# Controller.net
KiCad netlist of a schematic drawn in Altium Designer
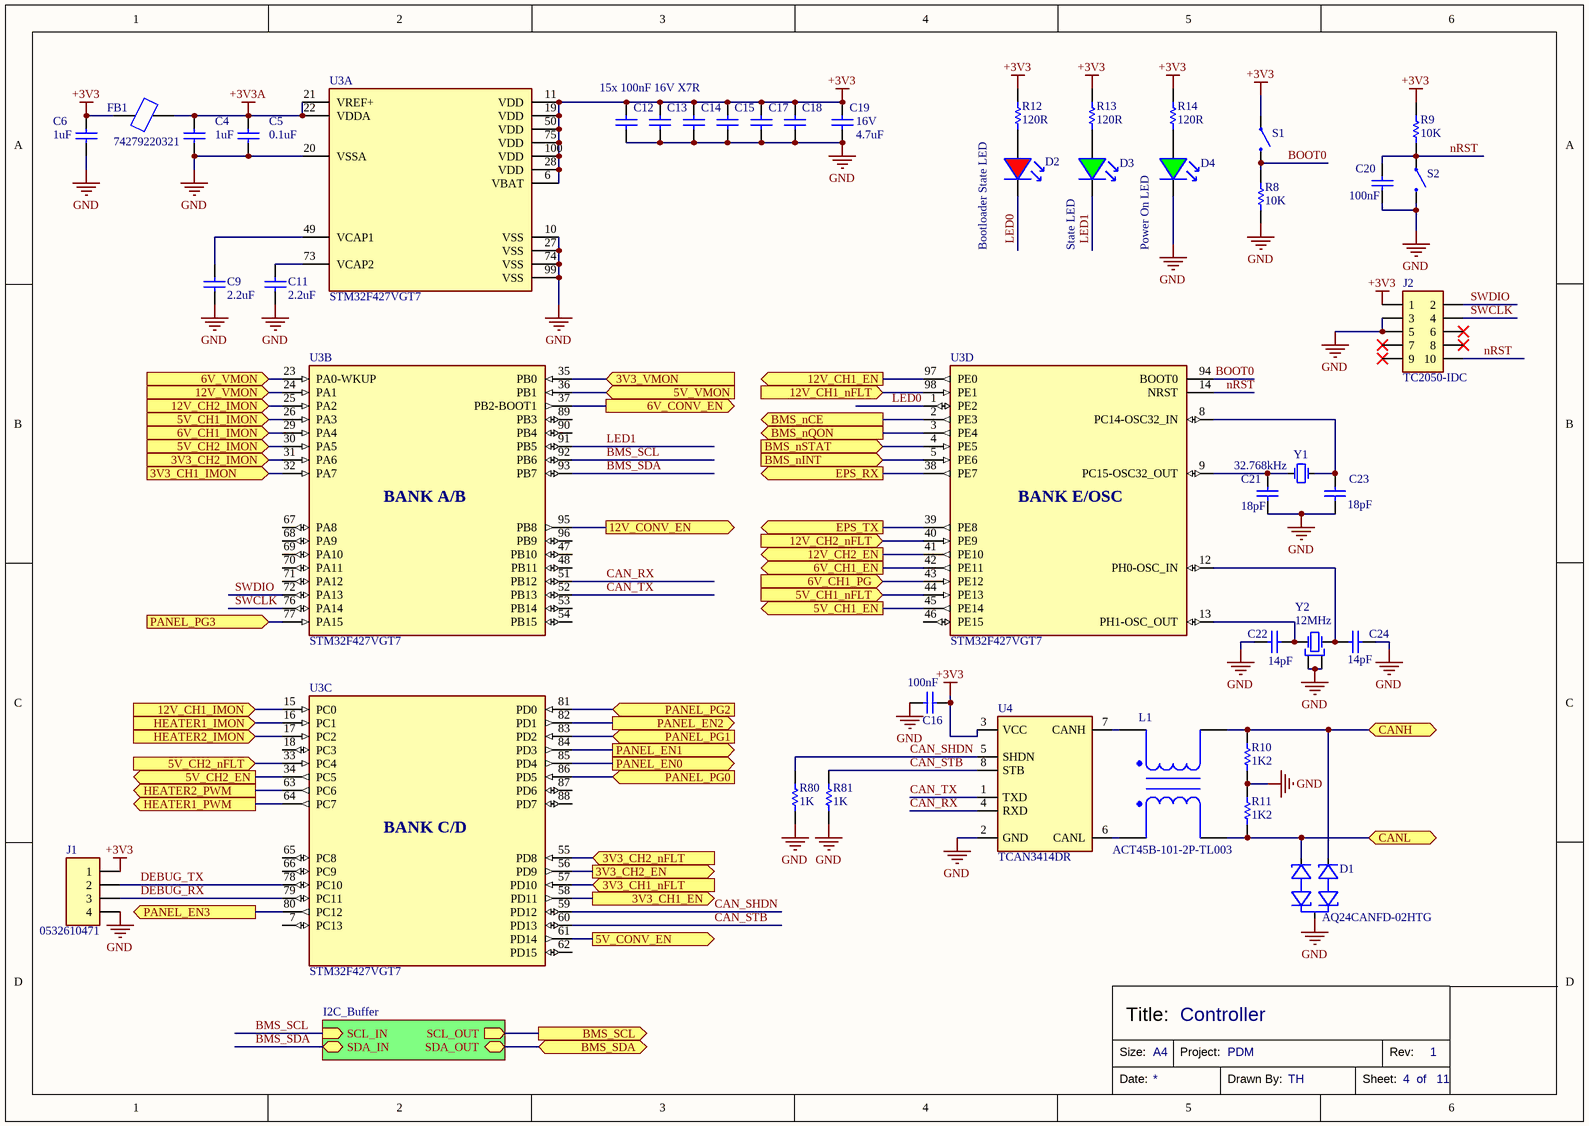
[diagram p0: Controller.SchDoc]

(export (version "E")
  (design (tool "Eeschema 10.0.6"))
  (components
    (comp (ref "C4")
      (value "CL10B105KO8NNNC")
      (footprint "CAPC0603X040")
      (description "1 µF ±10% 16V Ceramic Capacitor X7R 0603 (1608 Metric)")
      (fields
        (field (name "TOLERANCE") "10%")
        (field (name "DISTRIBUTOR PART NUMBER") "1276-1019-1-ND")
        (field (name "CAPACITANCE") "1uF")
      )
      (libsource (lib "Ahristi_Library") (part "CAPC0603"))
    )
    (comp (ref "C5")
      (value "CL05B104KB5NNNC")
      (footprint "CAPC0402X020")
      (description "0.1 µF ±10% 50V Ceramic Capacitor X7R 0402 (1005 Metric)")
      (fields
        (field (name "TOLERANCE") "10%")
        (field (name "DISTRIBUTOR PART NUMBER") "1276-CL05B104KB5NNNCCT-ND")
        (field (name "CAPACITANCE") "0.1uF")
      )
      (libsource (lib "Ahristi_Library") (part "CL05B104KB5NNNC"))
    )
    (comp (ref "C6")
      (value "CL10B105KO8NNNC")
      (footprint "CAPC0603X040")
      (description "1 µF ±10% 16V Ceramic Capacitor X7R 0603 (1608 Metric)")
      (fields
        (field (name "TOLERANCE") "10%")
        (field (name "DISTRIBUTOR PART NUMBER") "1276-1019-1-ND")
        (field (name "CAPACITANCE") "1uF")
      )
      (libsource (lib "Ahristi_Library") (part "CAPC0603"))
    )
    (comp (ref "C9")
      (value "CL21A225KBFNNNE")
      (footprint "CAPC0805X060")
      (description "2.2uF ±10% 25V Ceramic Capacitor X7R 0805 (2012 Metric)")
      (fields
        (field (name "DISTRIBUTOR PART NUMBER") "1276-6702-1-ND")
        (field (name "TOLERANCE") "10%")
        (field (name "CAPACITANCE") "2.2uF")
      )
      (libsource (lib "Ahristi_Library") (part "CL21A225KBFNNNE"))
    )
    (comp (ref "C11")
      (value "CL21A225KBFNNNE")
      (footprint "CAPC0805X060")
      (description "2.2uF ±10% 25V Ceramic Capacitor X7R 0805 (2012 Metric)")
      (fields
        (field (name "DISTRIBUTOR PART NUMBER") "1276-6702-1-ND")
        (field (name "TOLERANCE") "10%")
        (field (name "CAPACITANCE") "2.2uF")
      )
      (libsource (lib "Ahristi_Library") (part "CL21A225KBFNNNE"))
    )
    (comp (ref "C12")
      (value "CL05B104KB5NNNC")
      (footprint "CAPC0402X020")
      (description "0.1 µF ±10% 50V Ceramic Capacitor X7R 0402 (1005 Metric)")
      (fields
        (field (name "TOLERANCE") "10%")
        (field (name "DISTRIBUTOR PART NUMBER") "1276-CL05B104KB5NNNCCT-ND")
      )
      (libsource (lib "Ahristi_Library") (part "CL05B104KB5NNNC"))
    )
    (comp (ref "C13")
      (value "CL05B104KB5NNNC")
      (footprint "CAPC0402X020")
      (description "0.1 µF ±10% 50V Ceramic Capacitor X7R 0402 (1005 Metric)")
      (fields
        (field (name "TOLERANCE") "10%")
        (field (name "DISTRIBUTOR PART NUMBER") "1276-CL05B104KB5NNNCCT-ND")
      )
      (libsource (lib "Ahristi_Library") (part "CL05B104KB5NNNC"))
    )
    (comp (ref "C14")
      (value "CL05B104KB5NNNC")
      (footprint "CAPC0402X020")
      (description "0.1 µF ±10% 50V Ceramic Capacitor X7R 0402 (1005 Metric)")
      (fields
        (field (name "TOLERANCE") "10%")
        (field (name "DISTRIBUTOR PART NUMBER") "1276-CL05B104KB5NNNCCT-ND")
      )
      (libsource (lib "Ahristi_Library") (part "CL05B104KB5NNNC"))
    )
    (comp (ref "C15")
      (value "CL05B104KB5NNNC")
      (footprint "CAPC0402X020")
      (description "0.1 µF ±10% 50V Ceramic Capacitor X7R 0402 (1005 Metric)")
      (fields
        (field (name "TOLERANCE") "10%")
        (field (name "DISTRIBUTOR PART NUMBER") "1276-CL05B104KB5NNNCCT-ND")
      )
      (libsource (lib "Ahristi_Library") (part "CL05B104KB5NNNC"))
    )
    (comp (ref "C16")
      (value "C0603C104K5RACTU")
      (footprint "CAPC0603X040")
      (description "0.1 µF ±10% 50V Ceramic Capacitor X7R 0603 (1608 Metric)")
      (fields
        (field (name "TOLERANCE") "10%")
        (field (name "DISTRIBUTOR PART NUMBER") "399-C0603C104K5RACTUCT-ND")
        (field (name "CAPACITANCE") "100nF")
      )
      (libsource (lib "Ahristi_Library") (part "C0603C104K5RACTU"))
    )
    (comp (ref "C17")
      (value "CL05B104KB5NNNC")
      (footprint "CAPC0402X020")
      (description "0.1 µF ±10% 50V Ceramic Capacitor X7R 0402 (1005 Metric)")
      (fields
        (field (name "TOLERANCE") "10%")
        (field (name "DISTRIBUTOR PART NUMBER") "1276-CL05B104KB5NNNCCT-ND")
      )
      (libsource (lib "Ahristi_Library") (part "CL05B104KB5NNNC"))
    )
    (comp (ref "C18")
      (value "CL05B104KB5NNNC")
      (footprint "CAPC0402X020")
      (description "0.1 µF ±10% 50V Ceramic Capacitor X7R 0402 (1005 Metric)")
      (fields
        (field (name "TOLERANCE") "10%")
        (field (name "DISTRIBUTOR PART NUMBER") "1276-CL05B104KB5NNNCCT-ND")
      )
      (libsource (lib "Ahristi_Library") (part "CL05B104KB5NNNC"))
    )
    (comp (ref "C19")
      (value "CL21B475KOFNFNE")
      (footprint "CAPC0805X060")
      (description "4.7 µF ±10% 16V Ceramic Capacitor X7R 0805 (2012 Metric)")
      (fields
        (field (name "DISTRIBUTOR PART NUMBER") "1276-2970-1-ND")
        (field (name "TOLERANCE") "10%")
        (field (name "VOLTAGE RATING") "16V")
        (field (name "CAPACITANCE") "4.7uF")
      )
      (libsource (lib "Ahristi_Library") (part "CL21B475KOFNFNE"))
    )
    (comp (ref "C20")
      (value "C0603C104K5RACTU")
      (footprint "CAPC0603X040")
      (description "0.1 µF ±10% 50V Ceramic Capacitor X7R 0603 (1608 Metric)")
      (fields
        (field (name "TOLERANCE") "10%")
        (field (name "DISTRIBUTOR PART NUMBER") "399-C0603C104K5RACTUCT-ND")
        (field (name "CAPACITANCE") "100nF")
      )
      (libsource (lib "Ahristi_Library") (part "C0603C104K5RACTU"))
    )
    (comp (ref "C21")
      (value "KGM05ACG1H180FH")
      (footprint "CAPC0402X020")
      (description "18 pF ±1% 50V Ceramic Capacitor C0G, NP0 0402 (1005 Metric)")
      (fields
        (field (name "TOLERANCE") "1%")
        (field (name "DISTRIBUTOR PART NUMBER") "478-KGM05ACG1H180FHCT-ND")
        (field (name "CAPACITANCE") "18pF")
      )
      (libsource (lib "Ahristi_Library") (part "CAPC0402"))
    )
    (comp (ref "C22")
      (value "GJM1555C1H140FB01D")
      (footprint "CAPC0402X020")
      (description "14 pF ±1% 50V Ceramic Capacitor C0G, NP0 0402 (1005 Metric)")
      (fields
        (field (name "TOLERANCE") "1%")
        (field (name "DISTRIBUTOR PART NUMBER") "2266-GJM1555C1H140FB01DTR-ND")
        (field (name "CAPACITANCE") "14pF")
      )
      (libsource (lib "Ahristi_Library") (part "CAPC0402"))
    )
    (comp (ref "C23")
      (value "KGM05ACG1H180FH")
      (footprint "CAPC0402X020")
      (description "18 pF ±1% 50V Ceramic Capacitor C0G, NP0 0402 (1005 Metric)")
      (fields
        (field (name "TOLERANCE") "1%")
        (field (name "DISTRIBUTOR PART NUMBER") "478-KGM05ACG1H180FHCT-ND")
        (field (name "CAPACITANCE") "18pF")
      )
      (libsource (lib "Ahristi_Library") (part "CAPC0402"))
    )
    (comp (ref "C24")
      (value "GJM1555C1H140FB01D")
      (footprint "CAPC0402X020")
      (description "14 pF ±1% 50V Ceramic Capacitor C0G, NP0 0402 (1005 Metric)")
      (fields
        (field (name "TOLERANCE") "1%")
        (field (name "DISTRIBUTOR PART NUMBER") "2266-GJM1555C1H140FB01DTR-ND")
        (field (name "CAPACITANCE") "14pF")
      )
      (libsource (lib "Ahristi_Library") (part "CAPC0402"))
    )
    (comp (ref "D1")
      (value "AQ24CANFD-02HTG")
      (footprint "SOT23-3 IC")
      (description "50V Clamp 3A (8/20µs) Ipp Tvs Diode Surface Mount SOT-23-3")
      (fields (field (name "DISTRIBUTOR PART NUMBER") "F10993CT-ND"))
      (libsource (lib "Ahristi_Library") (part "AQ24CANFD-02HTG"))
    )
    (comp (ref "D2")
      (value "LTST-C170EKT")
      (footprint "LEDR_0805")
      (description "Red 621nm LED Indication - Discrete 2V 0805 (2012 Metric)")
      (fields (field (name "DISTRIBUTOR PART NUMBER") "160-1178-1-ND"))
      (libsource (lib "Ahristi_Library") (part "LEDR0805"))
    )
    (comp (ref "D3")
      (value "LTST-C170GKT")
      (footprint "LEDG_0805")
      (description "Green 569nm LED Indication - Discrete 2.1V 0805 (2012 Metric)")
      (fields (field (name "DISTRIBUTOR PART NUMBER") "160-1179-1-ND"))
      (libsource (lib "Ahristi_Library") (part "LEDG0805"))
    )
    (comp (ref "D4")
      (value "LTST-C170GKT")
      (footprint "LEDG_0805")
      (description "Green 569nm LED Indication - Discrete 2.1V 0805 (2012 Metric)")
      (fields (field (name "DISTRIBUTOR PART NUMBER") "160-1179-1-ND"))
      (libsource (lib "Ahristi_Library") (part "LEDG0805"))
    )
    (comp (ref "FB1")
      (value "74279220321")
      (footprint "74279220321")
      (description "Ferrite Bead 320 Ohms @ 100 MHz 1 Ferrite Bead 0805 (2012 Metric) 2.5A 50mOhm")
      (fields (field (name "DISTRIBUTOR PART NUMBER") "732-6125-1-ND"))
      (libsource (lib "Ahristi_Library") (part "74279220321"))
    )
    (comp (ref "J1")
      (value "0532610471")
      (footprint "0532610471")
      (description "Connector Header Surface Mount, Right Angle 4 position 0.049\" (1.25mm) Molex Picoblade")
      (fields (field (name "DISTRIBUTOR PART NUMBER") "WM7622CT-ND"))
      (libsource (lib "Ahristi_Library") (part "0532610471"))
    )
    (comp (ref "J2")
      (value "TC2050-IDC")
      (footprint "TC2050-IDC")
      (description "JTAG Pogo Programmer Pads")
      (libsource (lib "Ahristi_Library") (part "TC2050-IDC"))
    )
    (comp (ref "L1")
      (value "ACT45B-101-2P-TL003")
      (footprint "ACT45B-101-2P-TL003")
      (description "Common Mode Choke 100 µH @ 100 kHz 2 Line Surface Mount 5.8 kOhms @ 10 MHz 150mA DCR 2Ohm")
      (fields (field (name "DISTRIBUTOR PART NUMBER") "445-3959-1-ND"))
      (libsource (lib "Ahristi_Library") (part "ACT45B-101-2P-TL003"))
    )
    (comp (ref "R8")
      (value "RMCF0805FT10K0")
      (footprint "RESC0805")
      (description "10 kOhms ±1% 0.125W, 1/8W Chip Resistor 0805 (2012 Metric) Automotive AEC-Q200 Thick Film")
      (fields
        (field (name "TOLERANCE") "1%")
        (field (name "DISTRIBUTOR PART NUMBER") "RMCF0805FT10K0CT-ND")
        (field (name "RESISTANCE") "10K")
      )
      (libsource (lib "Ahristi_Library") (part "RMCF0805FT10K0"))
    )
    (comp (ref "R9")
      (value "RMCF0805FT10K0")
      (footprint "RESC0805")
      (description "10 kOhms ±1% 0.125W, 1/8W Chip Resistor 0805 (2012 Metric) Automotive AEC-Q200 Thick Film")
      (fields
        (field (name "TOLERANCE") "1%")
        (field (name "DISTRIBUTOR PART NUMBER") "RMCF0805FT10K0CT-ND")
        (field (name "RESISTANCE") "10K")
      )
      (libsource (lib "Ahristi_Library") (part "RMCF0805FT10K0"))
    )
    (comp (ref "R10")
      (value "RMCF0603FT1K20")
      (footprint "RESC0603")
      (description "1.2 kOhms ±1% 0.1W, 1/10W Chip Resistor 0603 (1608 Metric) Automotive AEC-Q200 Thick Film")
      (fields
        (field (name "TOLERANCE") "1%")
        (field (name "DISTRIBUTOR PART NUMBER") "RMCF0603FT1K20CT-ND")
        (field (name "RESISTANCE") "1K2")
      )
      (libsource (lib "Ahristi_Library") (part "RMCF0603FT1K20"))
    )
    (comp (ref "R11")
      (value "RMCF0603FT1K20")
      (footprint "RESC0603")
      (description "1.2 kOhms ±1% 0.1W, 1/10W Chip Resistor 0603 (1608 Metric) Automotive AEC-Q200 Thick Film")
      (fields
        (field (name "TOLERANCE") "1%")
        (field (name "DISTRIBUTOR PART NUMBER") "RMCF0603FT1K20CT-ND")
        (field (name "RESISTANCE") "1K2")
      )
      (libsource (lib "Ahristi_Library") (part "RMCF0603FT1K20"))
    )
    (comp (ref "R12")
      (value "RMCF0805FT120R")
      (footprint "RESC0805")
      (description "120 Ohms ±1% 0.125W, 1/8W Chip Resistor 0805 (2012 Metric) Automotive AEC-Q200 Thick Film")
      (fields
        (field (name "TOLERANCE") "1%")
        (field (name "DISTRIBUTOR PART NUMBER") "738-RMCF0805FT120RCT-ND")
        (field (name "RESISTANCE") "120R")
      )
      (libsource (lib "Ahristi_Library") (part "RMCF0805FT120R"))
    )
    (comp (ref "R13")
      (value "RMCF0805FT120R")
      (footprint "RESC0805")
      (description "120 Ohms ±1% 0.125W, 1/8W Chip Resistor 0805 (2012 Metric) Automotive AEC-Q200 Thick Film")
      (fields
        (field (name "TOLERANCE") "1%")
        (field (name "DISTRIBUTOR PART NUMBER") "738-RMCF0805FT120RCT-ND")
        (field (name "RESISTANCE") "120R")
      )
      (libsource (lib "Ahristi_Library") (part "RMCF0805FT120R"))
    )
    (comp (ref "R14")
      (value "RMCF0805FT120R")
      (footprint "RESC0805")
      (description "120 Ohms ±1% 0.125W, 1/8W Chip Resistor 0805 (2012 Metric) Automotive AEC-Q200 Thick Film")
      (fields
        (field (name "TOLERANCE") "1%")
        (field (name "DISTRIBUTOR PART NUMBER") "738-RMCF0805FT120RCT-ND")
        (field (name "RESISTANCE") "120R")
      )
      (libsource (lib "Ahristi_Library") (part "RMCF0805FT120R"))
    )
    (comp (ref "R80")
      (value "RNCP0805FTD1K00")
      (footprint "RESC0805")
      (description "1 kOhms ±1% 0.25W, 1/4W Chip Resistor 0805 (2012 Metric) Anti-Sulfur Thin Film")
      (fields
        (field (name "TOLERANCE") "1%")
        (field (name "DISTRIBUTOR PART NUMBER") "RNCP0805FTD1K00CT-ND")
        (field (name "RESISTANCE") "1K")
      )
      (libsource (lib "Ahristi_Library") (part "RNCP0805FTD1K00"))
    )
    (comp (ref "R81")
      (value "RNCP0805FTD1K00")
      (footprint "RESC0805")
      (description "1 kOhms ±1% 0.25W, 1/4W Chip Resistor 0805 (2012 Metric) Anti-Sulfur Thin Film")
      (fields
        (field (name "TOLERANCE") "1%")
        (field (name "DISTRIBUTOR PART NUMBER") "RNCP0805FTD1K00CT-ND")
        (field (name "RESISTANCE") "1K")
      )
      (libsource (lib "Ahristi_Library") (part "RNCP0805FTD1K00"))
    )
    (comp (ref "S1")
      (value "B3U-1000P")
      (footprint "B3U-1000P")
      (description "Tactile Switch SPST-NO Top Actuated Surface Mount")
      (fields (field (name "DISTRIBUTOR PART NUMBER") "SW1020CT-ND"))
      (libsource (lib "Ahristi_Library") (part "B3U-1000P"))
    )
    (comp (ref "S2")
      (value "B3U-1000P")
      (footprint "B3U-1000P")
      (description "Tactile Switch SPST-NO Top Actuated Surface Mount")
      (fields (field (name "DISTRIBUTOR PART NUMBER") "SW1020CT-ND"))
      (libsource (lib "Ahristi_Library") (part "B3U-1000P"))
    )
    (comp (ref "U3")
      (value "STM32F427VGT7")
      (footprint "STM32F427VGT7")
      (description "ARM® Cortex®-M4 STM32F4 Microcontroller IC 32-Bit 180MHz 1MB (1M x 8) FLASH 100-LQFP (14x14)")
      (fields (field (name "DISTRIBUTOR PART NUMBER") "497-16769-ND"))
      (libsource (lib "Ahristi_Library") (part "STM32F427VGT7"))
    )
    (comp (ref "U4")
      (value "TCAN3414DR")
      (footprint "SOIC-8")
      (description "3.3 V CAN-FD transceiver, CAN/CAN-FD up to 8 Mb/s, ±58 V bus-fault tolerant, SOIC-8")
      (fields (field (name "DISTRIBUTOR PART NUMBER") "296-TCAN3414DRCT-ND"))
      (libsource (lib "Ahristi_Library") (part "TCAN3414DR"))
    )
    (comp (ref "Y1")
      (value "CM7VT1A32.768KHZ125PF20PPMTBQAT3")
      (footprint "CM7VT1A32.768KHZ125PF20PPMTBQAT3")
      (description "CRYSTAL 32.7680KHZ 12.5PF SMD")
      (fields
        (field (name "DISTRIBUTOR PART NUMBER") "2195-CM7VT1A32.768KHZ125PF20PPMTBQAT3CT-ND")
        (field (name "FREQUENCY") "32.768kHz")
      )
      (libsource (lib "Ahristi_Library") (part "CM7VT1A32.768KHZ125PF20PPMTBQAT3"))
    )
    (comp (ref "Y2")
      (value "830069882")
      (footprint "830069882")
      (description "Crystals 12.0 MHZ 18PF 20PPM 120OHM")
      (fields
        (field (name "DISTRIBUTOR PART NUMBER") "732-830069882CT-ND")
        (field (name "FREQUENCY") "12MHz")
      )
      (libsource (lib "Ahristi_Library") (part "830069882"))
    )
  )
  (nets
    (net (code "1") (name "+3V3") (class "Default")
      (node (ref "C12") (pin "2") (pinfunction "2_2") (pintype "passive"))
      (node (ref "C13") (pin "2") (pinfunction "2_2") (pintype "passive"))
      (node (ref "C14") (pin "2") (pinfunction "2_2") (pintype "passive"))
      (node (ref "C15") (pin "2") (pinfunction "2_2") (pintype "passive"))
      (node (ref "C16") (pin "2") (pinfunction "2_2") (pintype "passive"))
      (node (ref "C17") (pin "2") (pinfunction "2_2") (pintype "passive"))
      (node (ref "C18") (pin "2") (pinfunction "2_2") (pintype "passive"))
      (node (ref "C19") (pin "2") (pinfunction "2_2") (pintype "passive"))
      (node (ref "C6") (pin "2") (pinfunction "2_2") (pintype "passive"))
      (node (ref "FB1") (pin "1") (pinfunction "1_1") (pintype "passive"))
      (node (ref "J1") (pin "1") (pinfunction "1_1") (pintype "passive"))
      (node (ref "J2") (pin "1") (pinfunction "1_1") (pintype "passive"))
      (node (ref "R12") (pin "2") (pinfunction "2_2") (pintype "passive"))
      (node (ref "R13") (pin "2") (pinfunction "2_2") (pintype "passive"))
      (node (ref "R14") (pin "2") (pinfunction "2_2") (pintype "passive"))
      (node (ref "R9") (pin "2") (pinfunction "2_2") (pintype "passive"))
      (node (ref "S1") (pin "1") (pinfunction "1_1") (pintype "passive"))
      (node (ref "U3") (pin "100") (pinfunction "VDD_100") (pintype "passive"))
      (node (ref "U3") (pin "11") (pinfunction "VDD_11") (pintype "passive"))
      (node (ref "U3") (pin "19") (pinfunction "VDD_19") (pintype "passive"))
      (node (ref "U3") (pin "28") (pinfunction "VDD_28") (pintype "passive"))
      (node (ref "U3") (pin "50") (pinfunction "VDD_50") (pintype "passive"))
      (node (ref "U3") (pin "6") (pinfunction "VBAT_6") (pintype "passive"))
      (node (ref "U3") (pin "75") (pinfunction "VDD_75") (pintype "passive"))
      (node (ref "U4") (pin "3") (pinfunction "VCC_3") (pintype "passive"))
    )
    (net (code "2") (name "+3V3A") (class "Default")
      (node (ref "C4") (pin "2") (pinfunction "2_2") (pintype "passive"))
      (node (ref "C5") (pin "2") (pinfunction "2_2") (pintype "passive"))
      (node (ref "FB1") (pin "2") (pinfunction "2_2") (pintype "passive"))
      (node (ref "U3") (pin "21") (pinfunction "VREF+_21") (pintype "passive"))
      (node (ref "U3") (pin "22") (pinfunction "VDDA_22") (pintype "passive"))
    )
    (net (code "3") (name "/3V3_CH1_EN") (class "Default")
      (node (ref "U3") (pin "58") (pinfunction "PD11_58") (pintype "bidirectional"))
    )
    (net (code "4") (name "/3V3_CH1_IMON") (class "Default")
      (node (ref "U3") (pin "32") (pinfunction "PA7_32") (pintype "input"))
    )
    (net (code "5") (name "/3V3_CH1_nFLT") (class "Default")
      (node (ref "U3") (pin "57") (pinfunction "PD10_57") (pintype "bidirectional"))
    )
    (net (code "6") (name "/3V3_CH2_EN") (class "Default")
      (node (ref "U3") (pin "56") (pinfunction "PD9_56") (pintype "bidirectional"))
    )
    (net (code "7") (name "/3V3_CH2_IMON") (class "Default")
      (node (ref "U3") (pin "31") (pinfunction "PA6_31") (pintype "input"))
    )
    (net (code "8") (name "/3V3_CH2_nFLT") (class "Default")
      (node (ref "U3") (pin "55") (pinfunction "PD8_55") (pintype "bidirectional"))
    )
    (net (code "9") (name "/3V3_VMON") (class "Default")
      (node (ref "U3") (pin "35") (pinfunction "PB0_35") (pintype "input"))
    )
    (net (code "10") (name "/5V_CH1_EN") (class "Default")
      (node (ref "U3") (pin "45") (pinfunction "PE14_45") (pintype "bidirectional"))
    )
    (net (code "11") (name "/5V_CH1_IMON") (class "Default")
      (node (ref "U3") (pin "26") (pinfunction "PA3_26") (pintype "input"))
    )
    (net (code "12") (name "/5V_CH1_nFLT") (class "Default")
      (node (ref "U3") (pin "44") (pinfunction "PE13_44") (pintype "bidirectional"))
    )
    (net (code "13") (name "/5V_CH2_EN") (class "Default")
      (node (ref "U3") (pin "34") (pinfunction "PC5_34") (pintype "bidirectional"))
    )
    (net (code "14") (name "/5V_CH2_IMON") (class "Default")
      (node (ref "U3") (pin "30") (pinfunction "PA5_30") (pintype "input"))
    )
    (net (code "15") (name "/5V_CH2_nFLT") (class "Default")
      (node (ref "U3") (pin "33") (pinfunction "PC4_33") (pintype "bidirectional"))
    )
    (net (code "16") (name "/5V_CONV_EN") (class "Default")
      (node (ref "U3") (pin "61") (pinfunction "PD14_61") (pintype "bidirectional"))
    )
    (net (code "17") (name "/5V_VMON") (class "Default")
      (node (ref "U3") (pin "36") (pinfunction "PB1_36") (pintype "input"))
    )
    (net (code "18") (name "/6V_CH1_EN") (class "Default")
      (node (ref "U3") (pin "42") (pinfunction "PE11_42") (pintype "bidirectional"))
    )
    (net (code "19") (name "/6V_CH1_IMON") (class "Default")
      (node (ref "U3") (pin "29") (pinfunction "PA4_29") (pintype "input"))
    )
    (net (code "20") (name "/6V_CH1_PG") (class "Default")
      (node (ref "U3") (pin "43") (pinfunction "PE12_43") (pintype "bidirectional"))
    )
    (net (code "21") (name "/6V_CONV_EN") (class "Default")
      (node (ref "U3") (pin "37") (pinfunction "PB2-BOOT1_37") (pintype "output"))
    )
    (net (code "22") (name "/6V_VMON") (class "Default")
      (node (ref "U3") (pin "23") (pinfunction "PA0-WKUP_23") (pintype "input"))
    )
    (net (code "23") (name "/12V_CH1_EN") (class "Default")
      (node (ref "U3") (pin "97") (pinfunction "PE0_97") (pintype "bidirectional"))
    )
    (net (code "24") (name "/12V_CH1_IMON") (class "Default")
      (node (ref "U3") (pin "15") (pinfunction "PC0_15") (pintype "bidirectional"))
    )
    (net (code "25") (name "/12V_CH1_nFLT") (class "Default")
      (node (ref "U3") (pin "98") (pinfunction "PE1_98") (pintype "bidirectional"))
    )
    (net (code "26") (name "/12V_CH2_EN") (class "Default")
      (node (ref "U3") (pin "41") (pinfunction "PE10_41") (pintype "bidirectional"))
    )
    (net (code "27") (name "/12V_CH2_IMON") (class "Default")
      (node (ref "U3") (pin "25") (pinfunction "PA2_25") (pintype "input"))
    )
    (net (code "28") (name "/12V_CH2_nFLT") (class "Default")
      (node (ref "U3") (pin "40") (pinfunction "PE9_40") (pintype "bidirectional"))
    )
    (net (code "29") (name "/12V_CONV_EN") (class "Default")
      (node (ref "U3") (pin "95") (pinfunction "PB8_95") (pintype "output"))
    )
    (net (code "30") (name "/12V_VMON") (class "Default")
      (node (ref "U3") (pin "24") (pinfunction "PA1_24") (pintype "input"))
    )
    (net (code "31") (name "/BMS_SCL") (class "Default")
      (node (ref "U3") (pin "92") (pinfunction "PB6_92") (pintype "bidirectional"))
    )
    (net (code "32") (name "/BMS_SDA") (class "Default")
      (node (ref "U3") (pin "93") (pinfunction "PB7_93") (pintype "bidirectional"))
    )
    (net (code "33") (name "/BMS_nCE") (class "Default")
      (node (ref "U3") (pin "2") (pinfunction "PE3_2") (pintype "bidirectional"))
    )
    (net (code "34") (name "/BMS_nINT") (class "Default")
      (node (ref "U3") (pin "5") (pinfunction "PE6_5") (pintype "bidirectional"))
    )
    (net (code "35") (name "/BMS_nQON") (class "Default")
      (node (ref "U3") (pin "3") (pinfunction "PE4_3") (pintype "bidirectional"))
    )
    (net (code "36") (name "/BMS_nSTAT") (class "Default")
      (node (ref "U3") (pin "4") (pinfunction "PE5_4") (pintype "bidirectional"))
    )
    (net (code "37") (name "/BOOT0") (class "Default")
      (node (ref "R8") (pin "2") (pinfunction "2_2") (pintype "passive"))
      (node (ref "S1") (pin "2") (pinfunction "2_2") (pintype "passive"))
      (node (ref "U3") (pin "94") (pinfunction "BOOT0_94") (pintype "passive"))
    )
    (net (code "38") (name "/CANH") (class "Default")
      (node (ref "D1") (pin "1") (pinfunction "1_1") (pintype "passive"))
      (node (ref "L1") (pin "4") (pinfunction "4_4") (pintype "passive"))
      (node (ref "R10") (pin "2") (pinfunction "2_2") (pintype "passive"))
    )
    (net (code "39") (name "/CANL") (class "Default")
      (node (ref "D1") (pin "2") (pinfunction "2_2") (pintype "passive"))
      (node (ref "L1") (pin "3") (pinfunction "3_3") (pintype "passive"))
      (node (ref "R11") (pin "1") (pinfunction "1_1") (pintype "passive"))
    )
    (net (code "40") (name "/CAN_RX") (class "Default")
      (node (ref "U3") (pin "51") (pinfunction "PB12_51") (pintype "bidirectional"))
      (node (ref "U4") (pin "4") (pinfunction "RXD_4") (pintype "passive"))
    )
    (net (code "41") (name "/CAN_SHDN") (class "Default")
      (node (ref "R80") (pin "2") (pinfunction "2_2") (pintype "passive"))
      (node (ref "U3") (pin "59") (pinfunction "PD12_59") (pintype "bidirectional"))
      (node (ref "U4") (pin "5") (pinfunction "SHDN_5") (pintype "passive"))
    )
    (net (code "42") (name "/CAN_STB") (class "Default")
      (node (ref "R81") (pin "2") (pinfunction "2_2") (pintype "passive"))
      (node (ref "U3") (pin "60") (pinfunction "PD13_60") (pintype "bidirectional"))
      (node (ref "U4") (pin "8") (pinfunction "STB_8") (pintype "passive"))
    )
    (net (code "43") (name "/CAN_TX") (class "Default")
      (node (ref "U3") (pin "52") (pinfunction "PB13_52") (pintype "bidirectional"))
      (node (ref "U4") (pin "1") (pinfunction "TXD_1") (pintype "passive"))
    )
    (net (code "44") (name "/DEBUG_RX") (class "Default")
      (node (ref "J1") (pin "3") (pinfunction "3_3") (pintype "passive"))
      (node (ref "U3") (pin "79") (pinfunction "PC11_79") (pintype "bidirectional"))
    )
    (net (code "45") (name "/DEBUG_TX") (class "Default")
      (node (ref "J1") (pin "2") (pinfunction "2_2") (pintype "passive"))
      (node (ref "U3") (pin "78") (pinfunction "PC10_78") (pintype "bidirectional"))
    )
    (net (code "46") (name "/EPS_RX") (class "Default")
      (node (ref "U3") (pin "38") (pinfunction "PE7_38") (pintype "bidirectional"))
    )
    (net (code "47") (name "/EPS_TX") (class "Default")
      (node (ref "U3") (pin "39") (pinfunction "PE8_39") (pintype "bidirectional"))
    )
    (net (code "48") (name "/HEATER1_IMON") (class "Default")
      (node (ref "U3") (pin "16") (pinfunction "PC1_16") (pintype "bidirectional"))
    )
    (net (code "49") (name "/HEATER1_PWM") (class "Default")
      (node (ref "U3") (pin "64") (pinfunction "PC7_64") (pintype "bidirectional"))
    )
    (net (code "50") (name "/HEATER2_IMON") (class "Default")
      (node (ref "U3") (pin "17") (pinfunction "PC2_17") (pintype "bidirectional"))
    )
    (net (code "51") (name "/HEATER2_PWM") (class "Default")
      (node (ref "U3") (pin "63") (pinfunction "PC6_63") (pintype "bidirectional"))
    )
    (net (code "52") (name "/LED0") (class "Default")
      (node (ref "D2") (pin "K") (pinfunction "K_K") (pintype "passive"))
      (node (ref "U3") (pin "1") (pinfunction "PE2_1") (pintype "bidirectional"))
    )
    (net (code "53") (name "/LED1") (class "Default")
      (node (ref "D3") (pin "K") (pinfunction "K_K") (pintype "passive"))
      (node (ref "U3") (pin "91") (pinfunction "PB5_91") (pintype "bidirectional"))
    )
    (net (code "54") (name "/PANEL_EN0") (class "Default")
      (node (ref "U3") (pin "85") (pinfunction "PD4_85") (pintype "bidirectional"))
    )
    (net (code "55") (name "/PANEL_EN1") (class "Default")
      (node (ref "U3") (pin "84") (pinfunction "PD3_84") (pintype "bidirectional"))
    )
    (net (code "56") (name "/PANEL_EN2") (class "Default")
      (node (ref "U3") (pin "82") (pinfunction "PD1_82") (pintype "bidirectional"))
    )
    (net (code "57") (name "/PANEL_EN3") (class "Default")
      (node (ref "U3") (pin "80") (pinfunction "PC12_80") (pintype "bidirectional"))
    )
    (net (code "58") (name "/PANEL_PG0") (class "Default")
      (node (ref "U3") (pin "86") (pinfunction "PD5_86") (pintype "bidirectional"))
    )
    (net (code "59") (name "/PANEL_PG1") (class "Default")
      (node (ref "U3") (pin "83") (pinfunction "PD2_83") (pintype "bidirectional"))
    )
    (net (code "60") (name "/PANEL_PG2") (class "Default")
      (node (ref "U3") (pin "81") (pinfunction "PD0_81") (pintype "bidirectional"))
    )
    (net (code "61") (name "/PANEL_PG3") (class "Default")
      (node (ref "U3") (pin "77") (pinfunction "PA15_77") (pintype "input"))
    )
    (net (code "62") (name "/SWCLK") (class "Default")
      (node (ref "J2") (pin "4") (pinfunction "4_4") (pintype "passive"))
      (node (ref "U3") (pin "76") (pinfunction "PA14_76") (pintype "bidirectional"))
    )
    (net (code "63") (name "/SWDIO") (class "Default")
      (node (ref "J2") (pin "2") (pinfunction "2_2") (pintype "passive"))
      (node (ref "U3") (pin "72") (pinfunction "PA13_72") (pintype "bidirectional"))
    )
    (net (code "64") (name "/nRST") (class "Default")
      (node (ref "C20") (pin "2") (pinfunction "2_2") (pintype "passive"))
      (node (ref "J2") (pin "10") (pinfunction "10_10") (pintype "passive"))
      (node (ref "R9") (pin "1") (pinfunction "1_1") (pintype "passive"))
      (node (ref "S2") (pin "1") (pinfunction "1_1") (pintype "passive"))
      (node (ref "U3") (pin "14") (pinfunction "NRST_14") (pintype "passive"))
    )
    (net (code "65") (name "GND") (class "Default")
      (node (ref "C11") (pin "1") (pinfunction "1_1") (pintype "passive"))
      (node (ref "C12") (pin "1") (pinfunction "1_1") (pintype "passive"))
      (node (ref "C13") (pin "1") (pinfunction "1_1") (pintype "passive"))
      (node (ref "C14") (pin "1") (pinfunction "1_1") (pintype "passive"))
      (node (ref "C15") (pin "1") (pinfunction "1_1") (pintype "passive"))
      (node (ref "C16") (pin "1") (pinfunction "1_1") (pintype "passive"))
      (node (ref "C17") (pin "1") (pinfunction "1_1") (pintype "passive"))
      (node (ref "C18") (pin "1") (pinfunction "1_1") (pintype "passive"))
      (node (ref "C19") (pin "1") (pinfunction "1_1") (pintype "passive"))
      (node (ref "C20") (pin "1") (pinfunction "1_1") (pintype "passive"))
      (node (ref "C21") (pin "1") (pinfunction "1_1") (pintype "passive"))
      (node (ref "C22") (pin "1") (pinfunction "1_1") (pintype "passive"))
      (node (ref "C23") (pin "2") (pinfunction "2_2") (pintype "passive"))
      (node (ref "C24") (pin "1") (pinfunction "1_1") (pintype "passive"))
      (node (ref "C4") (pin "1") (pinfunction "1_1") (pintype "passive"))
      (node (ref "C5") (pin "1") (pinfunction "1_1") (pintype "passive"))
      (node (ref "C6") (pin "1") (pinfunction "1_1") (pintype "passive"))
      (node (ref "C9") (pin "1") (pinfunction "1_1") (pintype "passive"))
      (node (ref "D1") (pin "3") (pinfunction "3_3") (pintype "passive"))
      (node (ref "D4") (pin "K") (pinfunction "K_K") (pintype "passive"))
      (node (ref "J1") (pin "4") (pinfunction "4_4") (pintype "passive"))
      (node (ref "J2") (pin "3") (pinfunction "3_3") (pintype "passive"))
      (node (ref "J2") (pin "5") (pinfunction "5_5") (pintype "passive"))
      (node (ref "R10") (pin "1") (pinfunction "1_1") (pintype "passive"))
      (node (ref "R11") (pin "2") (pinfunction "2_2") (pintype "passive"))
      (node (ref "R8") (pin "1") (pinfunction "1_1") (pintype "passive"))
      (node (ref "R80") (pin "1") (pinfunction "1_1") (pintype "passive"))
      (node (ref "R81") (pin "1") (pinfunction "1_1") (pintype "passive"))
      (node (ref "S2") (pin "2") (pinfunction "2_2") (pintype "passive"))
      (node (ref "U3") (pin "10") (pinfunction "VSS_10") (pintype "passive"))
      (node (ref "U3") (pin "20") (pinfunction "VSSA_20") (pintype "passive"))
      (node (ref "U3") (pin "27") (pinfunction "VSS_27") (pintype "passive"))
      (node (ref "U3") (pin "74") (pinfunction "VSS_74") (pintype "passive"))
      (node (ref "U3") (pin "99") (pinfunction "VSS_99") (pintype "passive"))
      (node (ref "U4") (pin "2") (pinfunction "GND_2") (pintype "passive"))
      (node (ref "Y2") (pin "2") (pinfunction "OSC1_2") (pintype "passive"))
      (node (ref "Y2") (pin "4") (pinfunction "OSC1_4") (pintype "passive"))
    )
    (net (code "66") (name "Net-(D2-PadA)") (class "Default")
      (node (ref "D2") (pin "A") (pinfunction "A_A") (pintype "passive"))
      (node (ref "R12") (pin "1") (pinfunction "1_1") (pintype "passive"))
    )
    (net (code "67") (name "Net-(D3-PadA)") (class "Default")
      (node (ref "D3") (pin "A") (pinfunction "A_A") (pintype "passive"))
      (node (ref "R13") (pin "1") (pinfunction "1_1") (pintype "passive"))
    )
    (net (code "68") (name "Net-(D4-PadA)") (class "Default")
      (node (ref "D4") (pin "A") (pinfunction "A_A") (pintype "passive"))
      (node (ref "R14") (pin "1") (pinfunction "1_1") (pintype "passive"))
    )
    (net (code "69") (name "Net-(U3A-VCAP1)") (class "Default")
      (node (ref "C9") (pin "2") (pinfunction "2_2") (pintype "passive"))
      (node (ref "U3") (pin "49") (pinfunction "VCAP1_49") (pintype "passive"))
    )
    (net (code "70") (name "Net-(U3A-VCAP2)") (class "Default")
      (node (ref "C11") (pin "2") (pinfunction "2_2") (pintype "passive"))
      (node (ref "U3") (pin "73") (pinfunction "VCAP2_73") (pintype "passive"))
    )
    (net (code "71") (name "Net-(U3D-PC14-OSC32_IN)") (class "Default")
      (node (ref "C23") (pin "1") (pinfunction "1_1") (pintype "passive"))
      (node (ref "U3") (pin "8") (pinfunction "PC14-OSC32_IN_8") (pintype "bidirectional"))
      (node (ref "Y1") (pin "2") (pinfunction "OSC2_2") (pintype "passive"))
    )
    (net (code "72") (name "Net-(U3D-PC15-OSC32_OUT)") (class "Default")
      (node (ref "C21") (pin "2") (pinfunction "2_2") (pintype "passive"))
      (node (ref "U3") (pin "9") (pinfunction "PC15-OSC32_OUT_9") (pintype "bidirectional"))
      (node (ref "Y1") (pin "1") (pinfunction "OSC1_1") (pintype "passive"))
    )
    (net (code "73") (name "Net-(U3D-PH0-OSC_IN)") (class "Default")
      (node (ref "C24") (pin "2") (pinfunction "2_2") (pintype "passive"))
      (node (ref "U3") (pin "12") (pinfunction "PH0-OSC_IN_12") (pintype "bidirectional"))
      (node (ref "Y2") (pin "3") (pinfunction "OSC2_3") (pintype "passive"))
    )
    (net (code "74") (name "Net-(U3D-PH1-OSC_OUT)") (class "Default")
      (node (ref "C22") (pin "2") (pinfunction "2_2") (pintype "passive"))
      (node (ref "U3") (pin "13") (pinfunction "PH1-OSC_OUT_13") (pintype "bidirectional"))
      (node (ref "Y2") (pin "1") (pinfunction "OSC1_1") (pintype "passive"))
    )
    (net (code "75") (name "Net-(U4-CANH)") (class "Default")
      (node (ref "L1") (pin "1") (pinfunction "1_1") (pintype "passive"))
      (node (ref "U4") (pin "7") (pinfunction "CANH_7") (pintype "passive"))
    )
    (net (code "76") (name "Net-(U4-CANL)") (class "Default")
      (node (ref "L1") (pin "2") (pinfunction "2_2") (pintype "passive"))
      (node (ref "U4") (pin "6") (pinfunction "CANL_6") (pintype "passive"))
    )
    (net (code "77") (name "unconnected-(J2-Pad6)") (class "Default")
      (node (ref "J2") (pin "6") (pinfunction "6_6") (pintype "passive+no_connect"))
    )
    (net (code "78") (name "unconnected-(J2-Pad7)") (class "Default")
      (node (ref "J2") (pin "7") (pinfunction "7_7") (pintype "passive+no_connect"))
    )
    (net (code "79") (name "unconnected-(J2-Pad8)") (class "Default")
      (node (ref "J2") (pin "8") (pinfunction "8_8") (pintype "passive+no_connect"))
    )
    (net (code "80") (name "unconnected-(J2-Pad9)") (class "Default")
      (node (ref "J2") (pin "9") (pinfunction "9_9") (pintype "passive+no_connect"))
    )
    (net (code "81") (name "unconnected-(U3B-PA8-Pad67)") (class "Default")
      (node (ref "U3") (pin "67") (pinfunction "PA8_67") (pintype "bidirectional"))
    )
    (net (code "82") (name "unconnected-(U3B-PA9-Pad68)") (class "Default")
      (node (ref "U3") (pin "68") (pinfunction "PA9_68") (pintype "bidirectional"))
    )
    (net (code "83") (name "unconnected-(U3B-PA10-Pad69)") (class "Default")
      (node (ref "U3") (pin "69") (pinfunction "PA10_69") (pintype "bidirectional"))
    )
    (net (code "84") (name "unconnected-(U3B-PA11-Pad70)") (class "Default")
      (node (ref "U3") (pin "70") (pinfunction "PA11_70") (pintype "bidirectional"))
    )
    (net (code "85") (name "unconnected-(U3B-PA12-Pad71)") (class "Default")
      (node (ref "U3") (pin "71") (pinfunction "PA12_71") (pintype "bidirectional"))
    )
    (net (code "86") (name "unconnected-(U3B-PB3-Pad89)") (class "Default")
      (node (ref "U3") (pin "89") (pinfunction "PB3_89") (pintype "bidirectional"))
    )
    (net (code "87") (name "unconnected-(U3B-PB4-Pad90)") (class "Default")
      (node (ref "U3") (pin "90") (pinfunction "PB4_90") (pintype "bidirectional"))
    )
    (net (code "88") (name "unconnected-(U3B-PB9-Pad96)") (class "Default")
      (node (ref "U3") (pin "96") (pinfunction "PB9_96") (pintype "bidirectional"))
    )
    (net (code "89") (name "unconnected-(U3B-PB10-Pad47)") (class "Default")
      (node (ref "U3") (pin "47") (pinfunction "PB10_47") (pintype "bidirectional"))
    )
    (net (code "90") (name "unconnected-(U3B-PB11-Pad48)") (class "Default")
      (node (ref "U3") (pin "48") (pinfunction "PB11_48") (pintype "bidirectional"))
    )
    (net (code "91") (name "unconnected-(U3B-PB14-Pad53)") (class "Default")
      (node (ref "U3") (pin "53") (pinfunction "PB14_53") (pintype "bidirectional"))
    )
    (net (code "92") (name "unconnected-(U3B-PB15-Pad54)") (class "Default")
      (node (ref "U3") (pin "54") (pinfunction "PB15_54") (pintype "bidirectional"))
    )
    (net (code "93") (name "unconnected-(U3C-PC3-Pad18)") (class "Default")
      (node (ref "U3") (pin "18") (pinfunction "PC3_18") (pintype "bidirectional"))
    )
    (net (code "94") (name "unconnected-(U3C-PC8-Pad65)") (class "Default")
      (node (ref "U3") (pin "65") (pinfunction "PC8_65") (pintype "bidirectional"))
    )
    (net (code "95") (name "unconnected-(U3C-PC9-Pad66)") (class "Default")
      (node (ref "U3") (pin "66") (pinfunction "PC9_66") (pintype "bidirectional"))
    )
    (net (code "96") (name "unconnected-(U3C-PC13-Pad7)") (class "Default")
      (node (ref "U3") (pin "7") (pinfunction "PC13_7") (pintype "bidirectional"))
    )
    (net (code "97") (name "unconnected-(U3C-PD6-Pad87)") (class "Default")
      (node (ref "U3") (pin "87") (pinfunction "PD6_87") (pintype "bidirectional"))
    )
    (net (code "98") (name "unconnected-(U3C-PD7-Pad88)") (class "Default")
      (node (ref "U3") (pin "88") (pinfunction "PD7_88") (pintype "bidirectional"))
    )
    (net (code "99") (name "unconnected-(U3C-PD15-Pad62)") (class "Default")
      (node (ref "U3") (pin "62") (pinfunction "PD15_62") (pintype "bidirectional"))
    )
    (net (code "100") (name "unconnected-(U3D-PE15-Pad46)") (class "Default")
      (node (ref "U3") (pin "46") (pinfunction "PE15_46") (pintype "bidirectional"))
    )
  )
)
